# L298N_Motor_Driver.net
KiCad netlist of a schematic drawn in Altium Designer
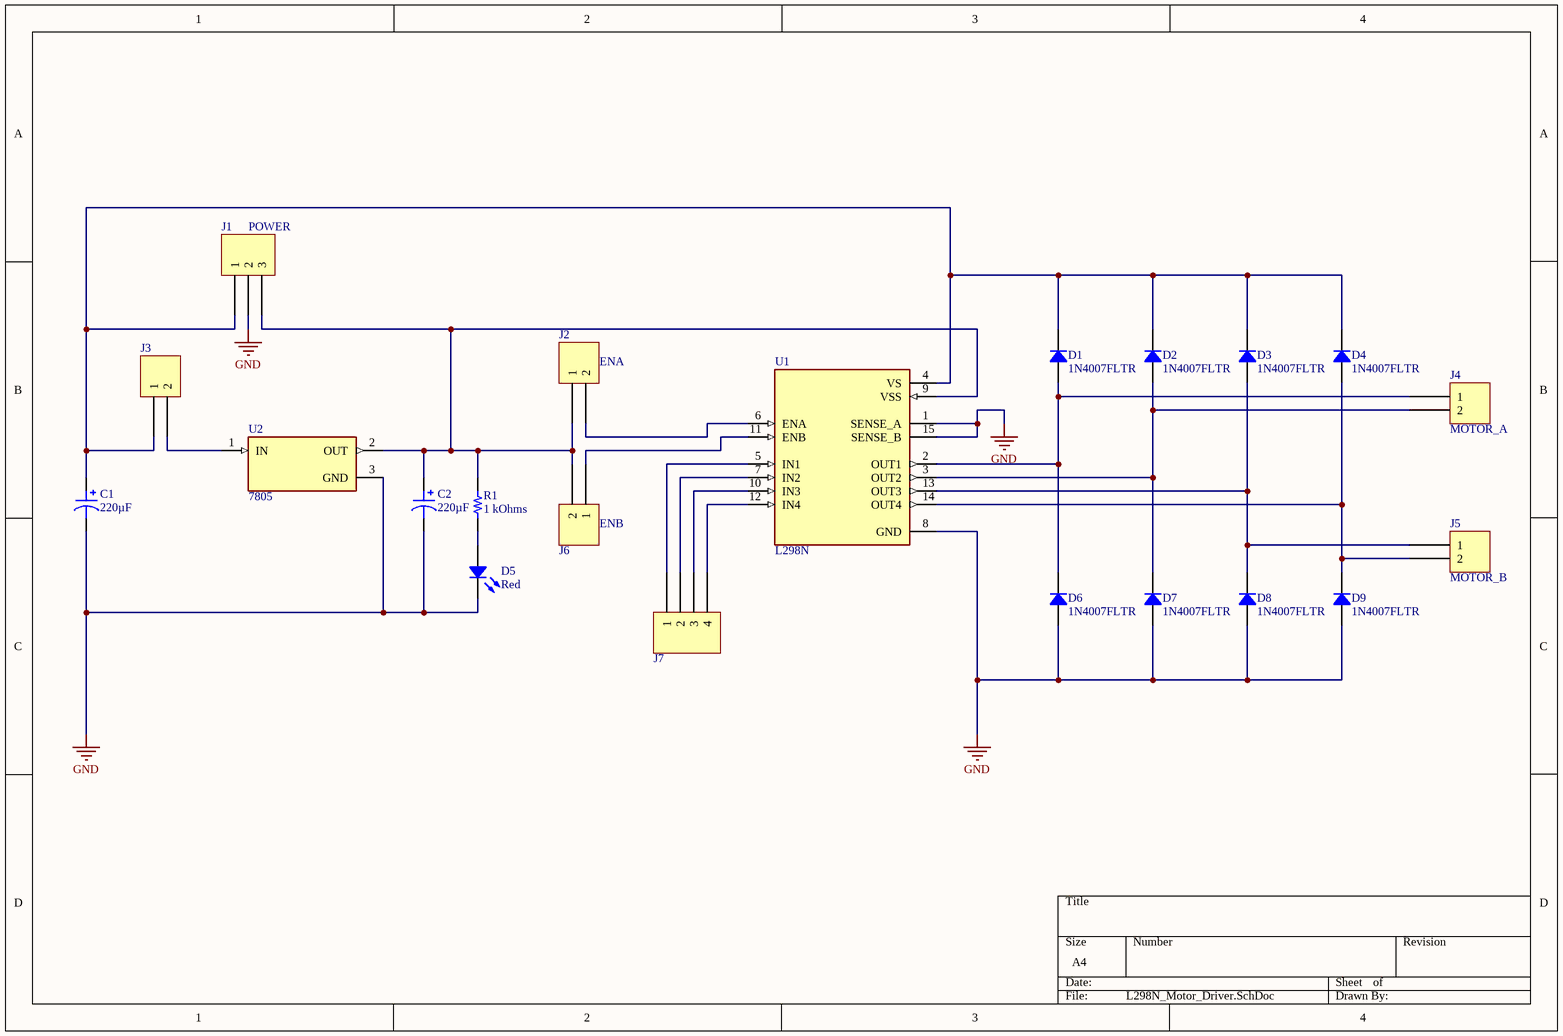
[diagram p0: L298N_Motor_Driver.SchDoc]

(export (version "E")
  (design (tool "Eeschema 10.0.6"))
  (components
    (comp (ref "C1")
      (value "220µF")
      (footprint "CAP ALSMD 8.3MM H10.5MM")
      (description "CAP ALUM 220UF 20% 35V SMD")
      (fields (field (name "PART NUMBER") "UUR1V221MNL6GS") (field (name "MANUFACTURER") "Nichicon"))
      (libsource (lib "Celestial Altium Library - altium_library") (part "Polarised Capacitor"))
    )
    (comp (ref "C2")
      (value "220µF")
      (footprint "CAP ALSMD 8.3MM H10.5MM")
      (description "CAP ALUM 220UF 20% 35V SMD")
      (fields (field (name "PART NUMBER") "UUR1V221MNL6GS") (field (name "MANUFACTURER") "Nichicon"))
      (libsource (lib "Celestial Altium Library - altium_library") (part "Polarised Capacitor"))
    )
    (comp (ref "D1")
      (value "1N4007FLTR")
      (footprint "SOD123F")
      (description "STANDARD RECTIFIER 1000V SOD-123")
      (fields (field (name "MANUFACTURER") "SMC Diode Solutions"))
      (libsource (lib "Celestial Altium Library - altium_library") (part "Diode"))
    )
    (comp (ref "D2")
      (value "1N4007FLTR")
      (footprint "SOD123F")
      (description "STANDARD RECTIFIER 1000V SOD-123")
      (fields (field (name "MANUFACTURER") "SMC Diode Solutions"))
      (libsource (lib "Celestial Altium Library - altium_library") (part "Diode"))
    )
    (comp (ref "D3")
      (value "1N4007FLTR")
      (footprint "SOD123F")
      (description "STANDARD RECTIFIER 1000V SOD-123")
      (fields (field (name "MANUFACTURER") "SMC Diode Solutions"))
      (libsource (lib "Celestial Altium Library - altium_library") (part "Diode"))
    )
    (comp (ref "D4")
      (value "1N4007FLTR")
      (footprint "SOD123F")
      (description "STANDARD RECTIFIER 1000V SOD-123")
      (fields (field (name "MANUFACTURER") "SMC Diode Solutions"))
      (libsource (lib "Celestial Altium Library - altium_library") (part "Diode"))
    )
    (comp (ref "D5")
      (value "Red")
      (footprint "LED 0805_2012 RED")
      (description "LED RED CLEAR 0805 SMD")
      (fields (field (name "PART NUMBER") "XZMDK54W-4") (field (name "MANUFACTURER") "SunLED"))
      (libsource (lib "Celestial Altium Library - altium_library") (part "LED"))
    )
    (comp (ref "D6")
      (value "1N4007FLTR")
      (footprint "SOD123F")
      (description "STANDARD RECTIFIER 1000V SOD-123")
      (fields (field (name "MANUFACTURER") "SMC Diode Solutions"))
      (libsource (lib "Celestial Altium Library - altium_library") (part "Diode"))
    )
    (comp (ref "D7")
      (value "1N4007FLTR")
      (footprint "SOD123F")
      (description "STANDARD RECTIFIER 1000V SOD-123")
      (fields (field (name "MANUFACTURER") "SMC Diode Solutions"))
      (libsource (lib "Celestial Altium Library - altium_library") (part "Diode"))
    )
    (comp (ref "D8")
      (value "1N4007FLTR")
      (footprint "SOD123F")
      (description "STANDARD RECTIFIER 1000V SOD-123")
      (fields (field (name "MANUFACTURER") "SMC Diode Solutions"))
      (libsource (lib "Celestial Altium Library - altium_library") (part "Diode"))
    )
    (comp (ref "D9")
      (value "1N4007FLTR")
      (footprint "SOD123F")
      (description "STANDARD RECTIFIER 1000V SOD-123")
      (fields (field (name "MANUFACTURER") "SMC Diode Solutions"))
      (libsource (lib "Celestial Altium Library - altium_library") (part "Diode"))
    )
    (comp (ref "J1")
      (value "POWER")
      (footprint "TE 282834-3")
      (description "TERM BLK 3P SIDE ENT 2.54MM PCB")
      (fields
        (field (name "PART NUMBER") "282834-3")
        (field (name "MANUFACTURER") "TE Connectivity AMP Connectors")
      )
      (libsource (lib "Celestial Altium Library - altium_library") (part "3 Pin"))
    )
    (comp (ref "J2")
      (value "ENA")
      (footprint "Header 2 PIN")
      (libsource (lib "L298N_Motor_Driver") (part "Header 2 PIN"))
    )
    (comp (ref "J3")
      (value "Header 2 PIN")
      (footprint "Header 2 PIN")
      (libsource (lib "L298N_Motor_Driver") (part "Header 2 PIN"))
    )
    (comp (ref "J4")
      (value "MOTOR_A")
      (footprint "TE 282834-2")
      (description "TERM BLK 2P SIDE ENT 2.54MM PCB")
      (fields
        (field (name "PART NUMBER") "282834-2")
        (field (name "MANUFACTURER") "TE Connectivity AMP Connectors")
      )
      (libsource (lib "Celestial Altium Library - altium_library") (part "2 Pin"))
    )
    (comp (ref "J5")
      (value "MOTOR_B")
      (footprint "TE 282834-2")
      (description "TERM BLK 2P SIDE ENT 2.54MM PCB")
      (fields
        (field (name "PART NUMBER") "282834-2")
        (field (name "MANUFACTURER") "TE Connectivity AMP Connectors")
      )
      (libsource (lib "Celestial Altium Library - altium_library") (part "2 Pin"))
    )
    (comp (ref "J6") (value "ENB") (footprint "Header 2 PIN") (libsource (lib "") (part "Header 2 PIN_1")))
    (comp (ref "J7")
      (value "Header 4 PIN")
      (footprint "Header 4 PIN")
      (libsource (lib "L298N_Motor_Driver") (part "Header 4 PIN"))
    )
    (comp (ref "R1")
      (value "1 kOhms")
      (footprint "RES 0805_2012")
      (description "RES SMD 1K OHM 0.01% 1/5W 0805")
      (fields
        (field (name "PART NUMBER") "Y40821K00000T9W")
        (field (name "MANUFACTURER") "Vishay Foil Resistors (Division of Vishay Precision Group)")
      )
      (libsource (lib "Celestial Altium Library - altium_library") (part "Resistor"))
    )
    (comp (ref "U1")
      (value "L298N")
      (footprint "L298N")
      (description "Motor Driver")
      (libsource (lib "L298N_Motor_Driver") (part "L298N"))
    )
    (comp (ref "U2")
      (value "7805")
      (footprint "7805CD2T")
      (description "Voltage Reg.")
      (libsource (lib "L298N_Motor_Driver") (part "7805"))
    )
  )
  (nets
    (net (code "1") (name "GND") (class "Default")
      (node (ref "C1") (pin "2") (pinfunction "2_2") (pintype "passive"))
      (node (ref "C2") (pin "2") (pinfunction "2_2") (pintype "passive"))
      (node (ref "D5") (pin "2") (pinfunction "2_2") (pintype "passive"))
      (node (ref "D6") (pin "1") (pinfunction "1_1") (pintype "passive"))
      (node (ref "D7") (pin "1") (pinfunction "1_1") (pintype "passive"))
      (node (ref "D8") (pin "1") (pinfunction "1_1") (pintype "passive"))
      (node (ref "D9") (pin "1") (pinfunction "1_1") (pintype "passive"))
      (node (ref "J1") (pin "2") (pinfunction "2_2") (pintype "passive"))
      (node (ref "U1") (pin "1") (pinfunction "SENSE_A_1") (pintype "passive"))
      (node (ref "U1") (pin "15") (pinfunction "SENSE_B_15") (pintype "passive"))
      (node (ref "U1") (pin "8") (pinfunction "GND_8") (pintype "power_in"))
      (node (ref "U2") (pin "3") (pinfunction "GND_3") (pintype "power_in"))
    )
    (net (code "2") (name "Net-(D5-Pad1)") (class "Default")
      (node (ref "D5") (pin "1") (pinfunction "1_1") (pintype "passive"))
      (node (ref "R1") (pin "1") (pinfunction "1_1") (pintype "passive"))
    )
    (net (code "3") (name "Net-(U1-ENA)") (class "Default")
      (node (ref "J2") (pin "2") (pinfunction "2_2") (pintype "passive"))
      (node (ref "U1") (pin "6") (pinfunction "ENA_6") (pintype "input"))
    )
    (net (code "4") (name "Net-(U1-ENB)") (class "Default")
      (node (ref "J6") (pin "1") (pinfunction "1_1") (pintype "passive"))
      (node (ref "U1") (pin "11") (pinfunction "ENB_11") (pintype "input"))
    )
    (net (code "5") (name "Net-(U1-IN1)") (class "Default")
      (node (ref "J7") (pin "1") (pinfunction "1_1") (pintype "passive"))
      (node (ref "U1") (pin "5") (pinfunction "IN1_5") (pintype "input"))
    )
    (net (code "6") (name "Net-(U1-IN2)") (class "Default")
      (node (ref "J7") (pin "2") (pinfunction "2_2") (pintype "passive"))
      (node (ref "U1") (pin "7") (pinfunction "IN2_7") (pintype "input"))
    )
    (net (code "7") (name "Net-(U1-IN3)") (class "Default")
      (node (ref "J7") (pin "3") (pinfunction "3_3") (pintype "passive"))
      (node (ref "U1") (pin "10") (pinfunction "IN3_10") (pintype "input"))
    )
    (net (code "8") (name "Net-(U1-IN4)") (class "Default")
      (node (ref "J7") (pin "4") (pinfunction "4_4") (pintype "passive"))
      (node (ref "U1") (pin "12") (pinfunction "IN4_12") (pintype "input"))
    )
    (net (code "9") (name "Net-(U1-OUT1)") (class "Default")
      (node (ref "D1") (pin "1") (pinfunction "1_1") (pintype "passive"))
      (node (ref "D6") (pin "2") (pinfunction "2_2") (pintype "passive"))
      (node (ref "J4") (pin "1") (pinfunction "1_1") (pintype "passive"))
      (node (ref "U1") (pin "2") (pinfunction "OUT1_2") (pintype "output"))
    )
    (net (code "10") (name "Net-(U1-OUT2)") (class "Default")
      (node (ref "D2") (pin "1") (pinfunction "1_1") (pintype "passive"))
      (node (ref "D7") (pin "2") (pinfunction "2_2") (pintype "passive"))
      (node (ref "J4") (pin "2") (pinfunction "2_2") (pintype "passive"))
      (node (ref "U1") (pin "3") (pinfunction "OUT2_3") (pintype "output"))
    )
    (net (code "11") (name "Net-(U1-OUT3)") (class "Default")
      (node (ref "D3") (pin "1") (pinfunction "1_1") (pintype "passive"))
      (node (ref "D8") (pin "2") (pinfunction "2_2") (pintype "passive"))
      (node (ref "J5") (pin "1") (pinfunction "1_1") (pintype "passive"))
      (node (ref "U1") (pin "13") (pinfunction "OUT3_13") (pintype "output"))
    )
    (net (code "12") (name "Net-(U1-OUT4)") (class "Default")
      (node (ref "D4") (pin "1") (pinfunction "1_1") (pintype "passive"))
      (node (ref "D9") (pin "2") (pinfunction "2_2") (pintype "passive"))
      (node (ref "J5") (pin "2") (pinfunction "2_2") (pintype "passive"))
      (node (ref "U1") (pin "14") (pinfunction "OUT4_14") (pintype "output"))
    )
    (net (code "13") (name "Net-(U1-VS)") (class "Default")
      (node (ref "C1") (pin "1") (pinfunction "1_1") (pintype "passive"))
      (node (ref "D1") (pin "2") (pinfunction "2_2") (pintype "passive"))
      (node (ref "D2") (pin "2") (pinfunction "2_2") (pintype "passive"))
      (node (ref "D3") (pin "2") (pinfunction "2_2") (pintype "passive"))
      (node (ref "D4") (pin "2") (pinfunction "2_2") (pintype "passive"))
      (node (ref "J1") (pin "1") (pinfunction "1_1") (pintype "passive"))
      (node (ref "J3") (pin "1") (pinfunction "1_1") (pintype "passive"))
      (node (ref "U1") (pin "4") (pinfunction "VS_4") (pintype "power_in"))
    )
    (net (code "14") (name "Net-(U1-VSS)") (class "Default")
      (node (ref "C2") (pin "1") (pinfunction "1_1") (pintype "passive"))
      (node (ref "J1") (pin "3") (pinfunction "3_3") (pintype "passive"))
      (node (ref "J2") (pin "1") (pinfunction "1_1") (pintype "passive"))
      (node (ref "J6") (pin "2") (pinfunction "2_2") (pintype "passive"))
      (node (ref "R1") (pin "2") (pinfunction "2_2") (pintype "passive"))
      (node (ref "U1") (pin "9") (pinfunction "VSS_9") (pintype "input"))
      (node (ref "U2") (pin "2") (pinfunction "OUT_2") (pintype "output"))
    )
    (net (code "15") (name "Net-(U2-IN)") (class "Default")
      (node (ref "J3") (pin "2") (pinfunction "2_2") (pintype "passive"))
      (node (ref "U2") (pin "1") (pinfunction "IN_1") (pintype "input"))
    )
  )
)
